# XIAO-HAT.net
KiCad netlist of a schematic drawn in Altium Designer
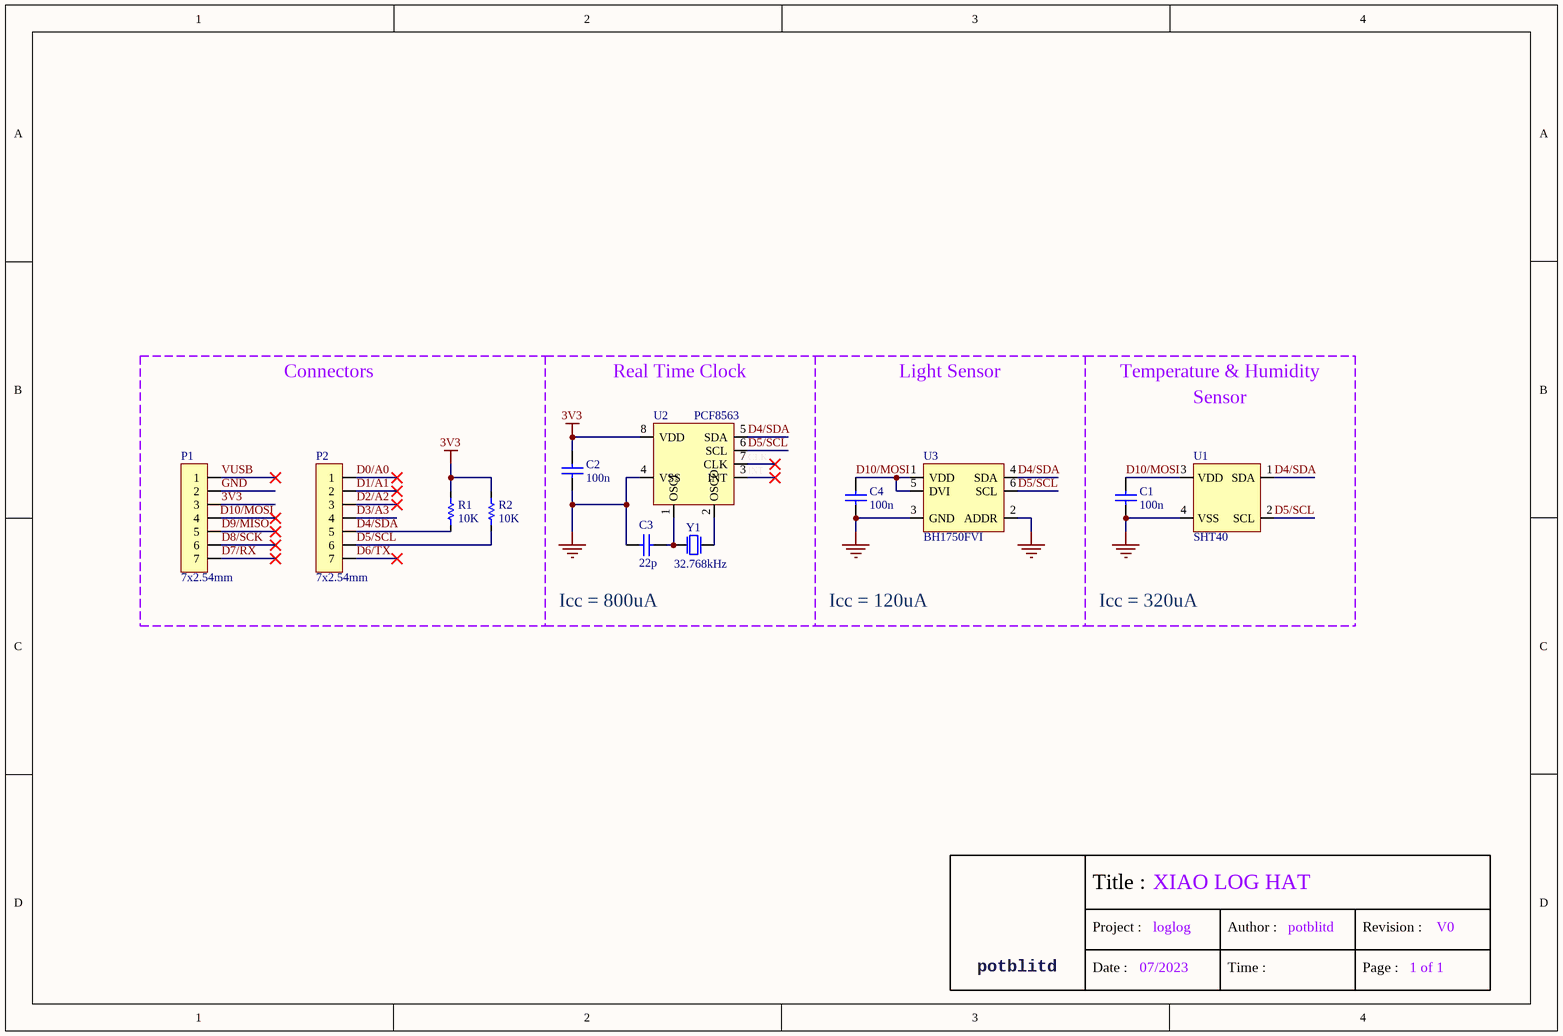
[diagram p0: XIAO-HAT.SchDoc]

(export (version "E")
  (design (tool "Eeschema 10.0.6"))
  (components
    (comp (ref "C1")
      (value "100n")
      (footprint "0603C")
      (description "Capacitor 100nF ±10% 50V")
      (fields (field (name "Comment") "Capacitor"))
      (libsource (lib "Simulation Generic Components") (part "Capacitor"))
    )
    (comp (ref "C2")
      (value "100n")
      (footprint "0603C")
      (description "Capacitor 100nF ±10% 50V")
      (fields (field (name "Comment") "Capacitor"))
      (libsource (lib "Simulation Generic Components") (part "Capacitor"))
    )
    (comp (ref "C3")
      (value "22p")
      (footprint "0603C")
      (description "Capacitor 22pF ±5% 50V")
      (fields (field (name "Comment") "Capacitor"))
      (libsource (lib "Simulation Generic Components") (part "Capacitor"))
    )
    (comp (ref "C4")
      (value "100n")
      (footprint "0603C")
      (description "Capacitor 100nF ±10% 50V")
      (fields (field (name "Comment") "Capacitor"))
      (libsource (lib "Simulation Generic Components") (part "Capacitor"))
    )
    (comp (ref "P1")
      (value "7x2.54mm")
      (footprint "7P-2.54mm-0.84")
      (description "General 7-pin connection")
      (libsource (lib "AltiumLib") (part "7-pins Header"))
    )
    (comp (ref "P2")
      (value "7x2.54mm")
      (footprint "7P-2.54mm-0.84")
      (description "General 7-pin connection")
      (libsource (lib "AltiumLib") (part "7-pins Header"))
    )
    (comp (ref "R1")
      (value "10K")
      (footprint "0603R")
      (description "Resistor 10kΩ ±1% 1/16W")
      (fields (field (name "Comment") "Resistor"))
      (libsource (lib "Simulation Generic Components") (part "RES"))
    )
    (comp (ref "R2")
      (value "10K")
      (footprint "0603R")
      (description "Resistor 10kΩ ±1% 1/16W")
      (fields (field (name "Comment") "Resistor"))
      (libsource (lib "Simulation Generic Components") (part "RES"))
    )
    (comp (ref "U1")
      (value "SHT40")
      (footprint "DFN-4-EP(1.5x1.5)")
      (description "SHT40 temperature and humidity sensor")
      (libsource (lib "AltiumLib") (part "SHT40"))
    )
    (comp (ref "U2")
      (value "PCF8563")
      (footprint "SOP-8")
      (description "IC real-time clock with alarm interrupt")
      (libsource (lib "AltiumLib") (part "RTC-8563"))
    )
    (comp (ref "U3")
      (value "BH1750FVI")
      (footprint "WSOF6")
      (description "Digital light sensor")
      (libsource (lib "AltiumLib") (part "BH1750"))
    )
    (comp (ref "Y1")
      (value "32.768kHz")
      (footprint "FC135")
      (description "Crystal oscillator 32.768kHz 20ppm 12.5pF")
      (fields (field (name "Comment") "Oscillator"))
      (libsource (lib "AltiumLib") (part "XO-2"))
    )
  )
  (nets
    (net (code "1") (name "/CLK") (class "Default")
      (node (ref "U2") (pin "7") (pinfunction "CLK_7") (pintype "passive+no_connect"))
    )
    (net (code "2") (name "/D0{slash}A0") (class "Default")
      (node (ref "P2") (pin "1") (pinfunction "1_1") (pintype "passive+no_connect"))
    )
    (net (code "3") (name "/D1{slash}A1") (class "Default")
      (node (ref "P2") (pin "2") (pinfunction "2_2") (pintype "passive+no_connect"))
    )
    (net (code "4") (name "/D2{slash}A2") (class "Default")
      (node (ref "P2") (pin "3") (pinfunction "3_3") (pintype "passive+no_connect"))
    )
    (net (code "5") (name "/D3{slash}A3") (class "Default")
      (node (ref "P2") (pin "4") (pinfunction "4_4") (pintype "passive"))
    )
    (net (code "6") (name "/D4{slash}SDA") (class "Default")
      (node (ref "P2") (pin "5") (pinfunction "5_5") (pintype "passive"))
      (node (ref "R1") (pin "1") (pinfunction "1_1") (pintype "passive"))
      (node (ref "U1") (pin "1") (pinfunction "SDA_1") (pintype "passive"))
      (node (ref "U2") (pin "5") (pinfunction "SDA_5") (pintype "passive"))
      (node (ref "U3") (pin "4") (pinfunction "SDA_4") (pintype "passive"))
    )
    (net (code "7") (name "/D5{slash}SCL") (class "Default")
      (node (ref "P2") (pin "6") (pinfunction "6_6") (pintype "passive"))
      (node (ref "R2") (pin "1") (pinfunction "1_1") (pintype "passive"))
      (node (ref "U1") (pin "2") (pinfunction "SCL_2") (pintype "passive"))
      (node (ref "U2") (pin "6") (pinfunction "SCL_6") (pintype "passive"))
      (node (ref "U3") (pin "6") (pinfunction "SCL_6") (pintype "passive"))
    )
    (net (code "8") (name "/D6{slash}TX") (class "Default")
      (node (ref "P2") (pin "7") (pinfunction "7_7") (pintype "passive+no_connect"))
    )
    (net (code "9") (name "/D7{slash}RX") (class "Default")
      (node (ref "P1") (pin "7") (pinfunction "7_7") (pintype "passive+no_connect"))
    )
    (net (code "10") (name "/D8{slash}SCK") (class "Default")
      (node (ref "P1") (pin "6") (pinfunction "6_6") (pintype "passive+no_connect"))
    )
    (net (code "11") (name "/D9{slash}MISO") (class "Default")
      (node (ref "P1") (pin "5") (pinfunction "5_5") (pintype "passive+no_connect"))
    )
    (net (code "12") (name "/D10{slash}MOSI") (class "Default")
      (node (ref "C1") (pin "1") (pinfunction "1_1") (pintype "passive"))
      (node (ref "C4") (pin "1") (pinfunction "1_1") (pintype "passive"))
      (node (ref "P1") (pin "4") (pinfunction "4_4") (pintype "passive"))
      (node (ref "U1") (pin "3") (pinfunction "VDD_3") (pintype "passive"))
      (node (ref "U3") (pin "1") (pinfunction "VDD_1") (pintype "passive"))
      (node (ref "U3") (pin "5") (pinfunction "DVI_5") (pintype "passive"))
    )
    (net (code "13") (name "/INT") (class "Default")
      (node (ref "U2") (pin "3") (pinfunction "INT_3") (pintype "passive+no_connect"))
    )
    (net (code "14") (name "/VUSB") (class "Default")
      (node (ref "P1") (pin "1") (pinfunction "1_1") (pintype "passive+no_connect"))
    )
    (net (code "15") (name "3V3") (class "Default")
      (node (ref "C2") (pin "1") (pinfunction "1_1") (pintype "passive"))
      (node (ref "P1") (pin "3") (pinfunction "3_3") (pintype "passive"))
      (node (ref "R1") (pin "2") (pinfunction "2_2") (pintype "passive"))
      (node (ref "R2") (pin "2") (pinfunction "2_2") (pintype "passive"))
      (node (ref "U2") (pin "8") (pinfunction "VDD_8") (pintype "passive"))
    )
    (net (code "16") (name "GND") (class "Default")
      (node (ref "C1") (pin "2") (pinfunction "2_2") (pintype "passive"))
      (node (ref "C2") (pin "2") (pinfunction "2_2") (pintype "passive"))
      (node (ref "C3") (pin "2") (pinfunction "2_2") (pintype "passive"))
      (node (ref "C4") (pin "2") (pinfunction "2_2") (pintype "passive"))
      (node (ref "P1") (pin "2") (pinfunction "2_2") (pintype "passive"))
      (node (ref "U1") (pin "4") (pinfunction "VSS_4") (pintype "passive"))
      (node (ref "U2") (pin "4") (pinfunction "VSS_4") (pintype "passive"))
      (node (ref "U3") (pin "2") (pinfunction "ADDR_2") (pintype "passive"))
      (node (ref "U3") (pin "3") (pinfunction "GND_3") (pintype "passive"))
    )
    (net (code "17") (name "Net-(U2-OSCI)") (class "Default")
      (node (ref "C3") (pin "1") (pinfunction "1_1") (pintype "passive"))
      (node (ref "U2") (pin "1") (pinfunction "OSCI_1") (pintype "passive"))
      (node (ref "Y1") (pin "2") (pinfunction "2_2") (pintype "passive"))
    )
    (net (code "18") (name "Net-(U2-OSCO)") (class "Default")
      (node (ref "U2") (pin "2") (pinfunction "OSCO_2") (pintype "passive"))
      (node (ref "Y1") (pin "1") (pinfunction "1_1") (pintype "passive"))
    )
  )
)
